# 07_-MCU.net
KiCad netlist of a schematic drawn in Altium Designer
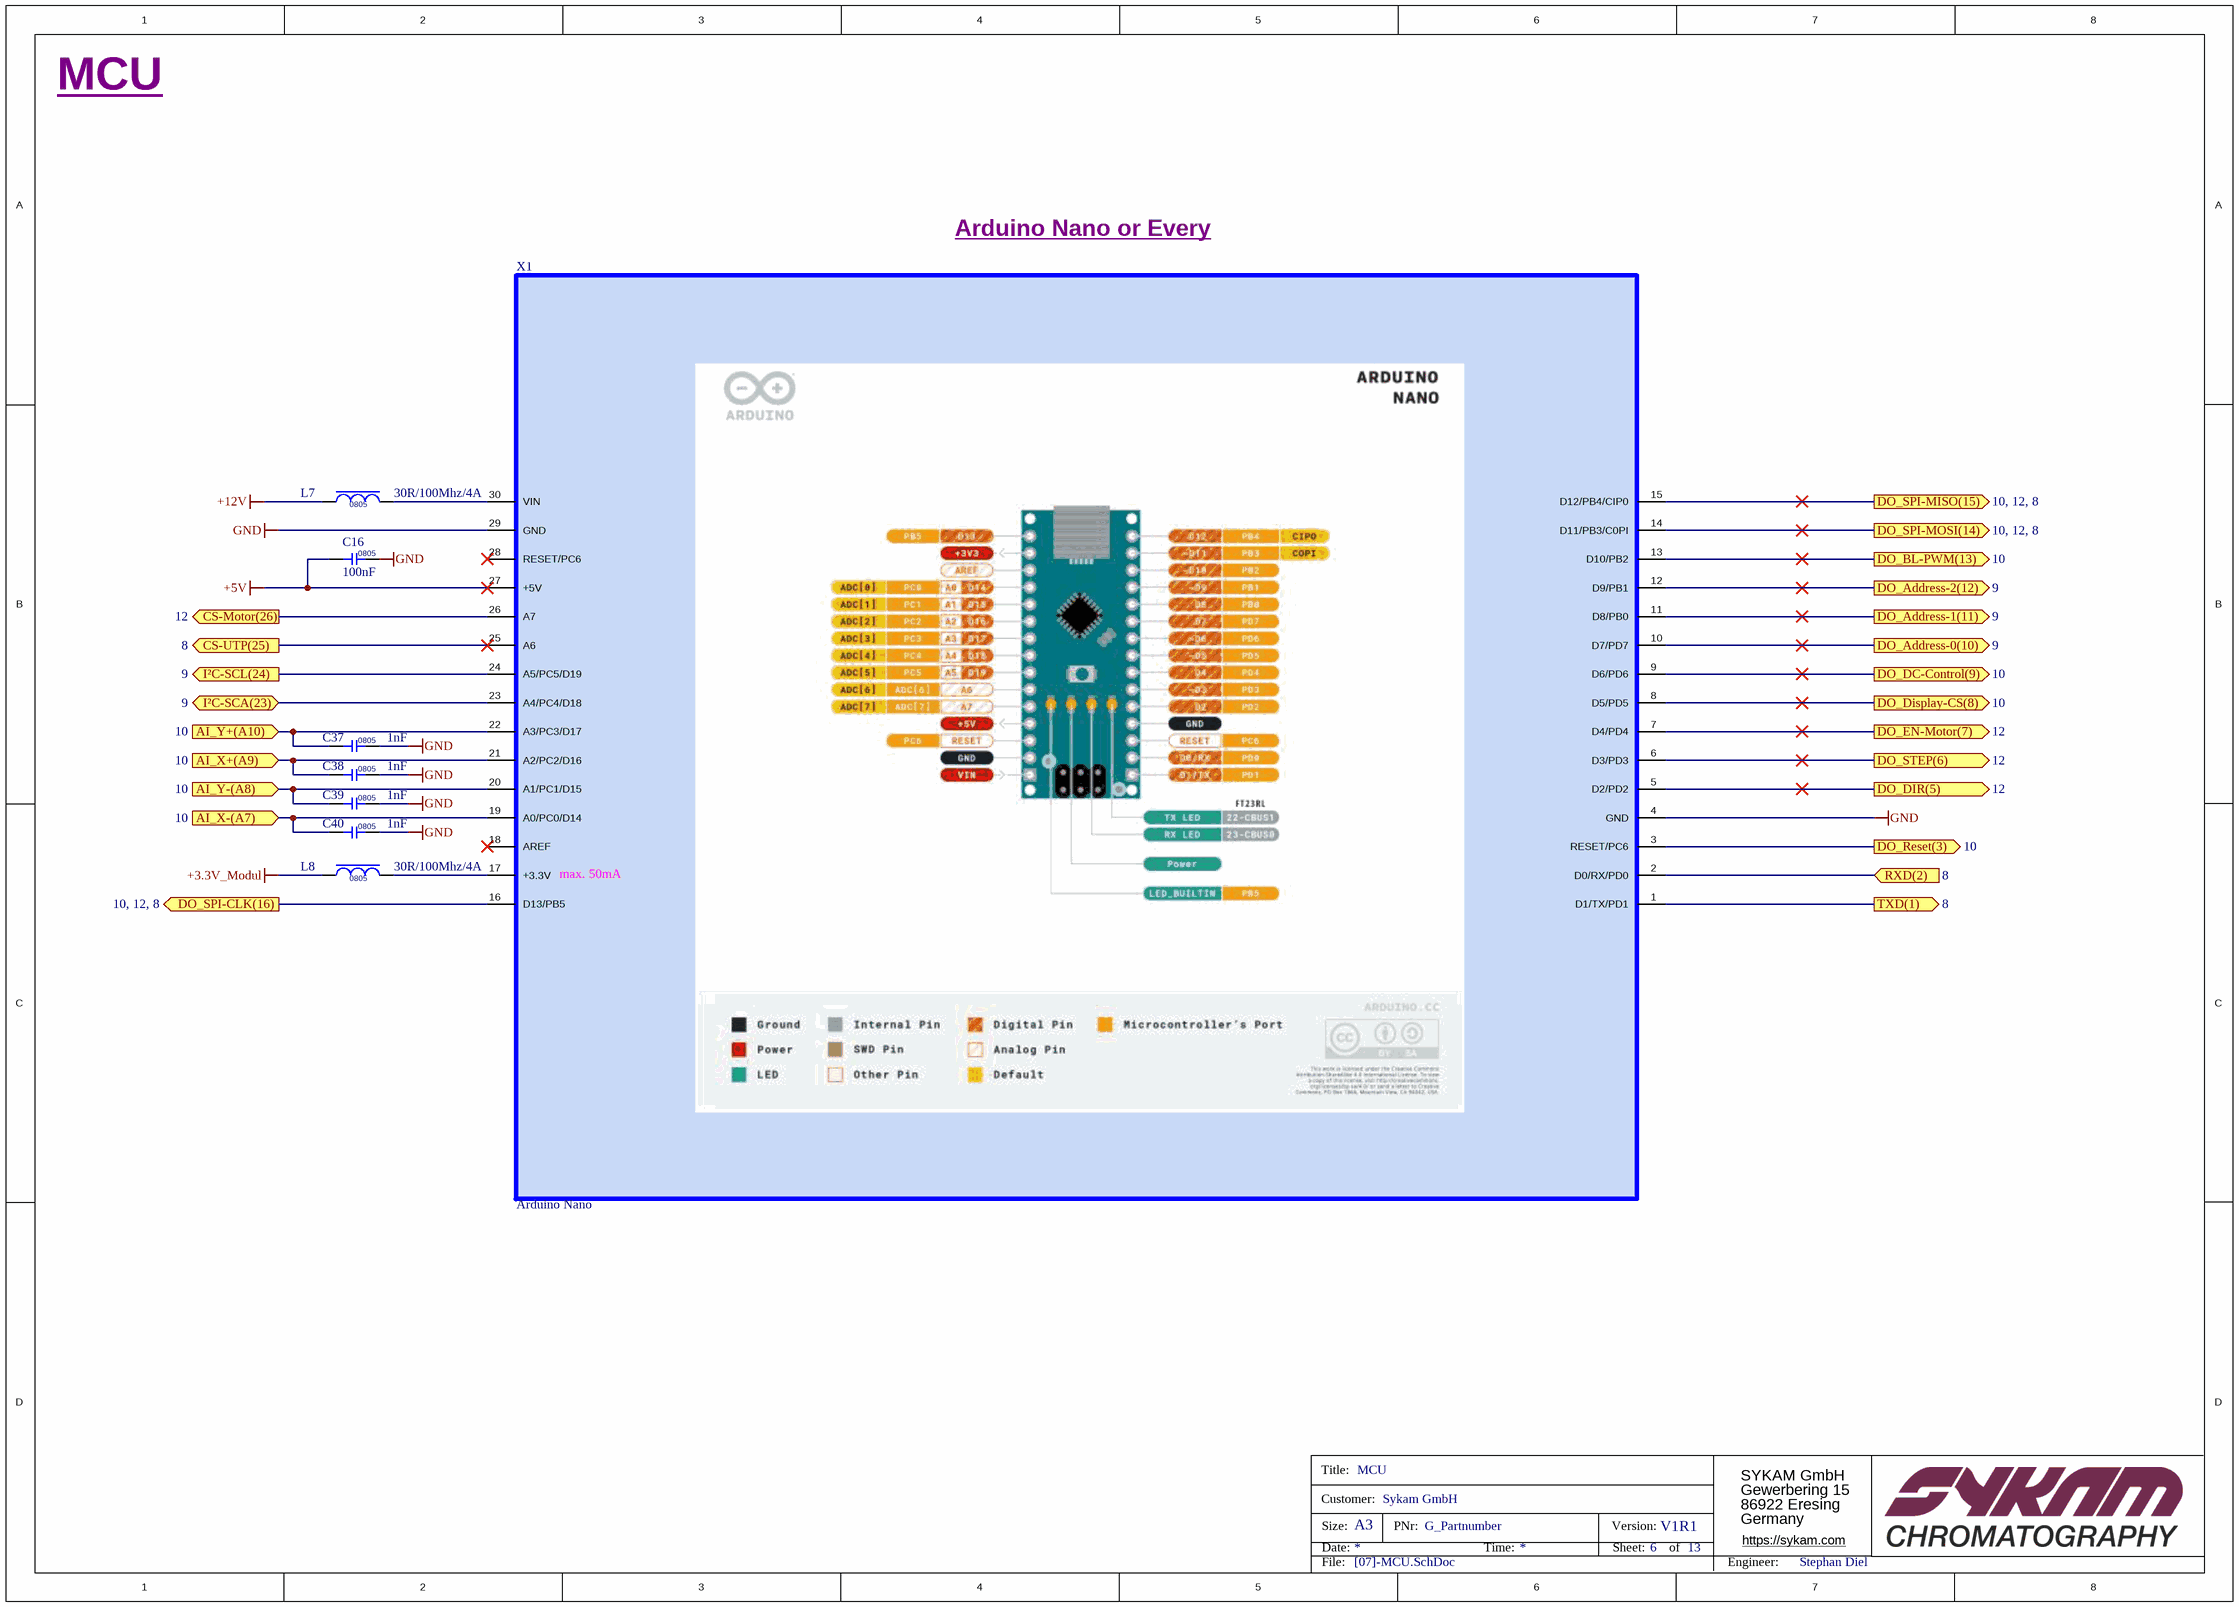
[diagram p0: [07]-MCU.SchDoc]

(export (version "E")
  (design (tool "Eeschema 10.0.6"))
  (components
    (comp (ref "C16")
      (value "100nF")
      (footprint "C0805")
      (description "CAP CER 0.1UF 50V X7R 0805")
      (fields
        (field (name "MANUFACTURER PART NUMBER") "CC0805KRX7R9BB104")
        (field (name "TOLERANCE") "10%")
        (field (name "PCBCHECKED") "initials after Checked")
        (field (name "SCHCHECKED") "Initials after checked")
      )
      (libsource (lib "ToradexMainBoard-V0I1") (part "C_100nF_CC0805KRX7R9BB104"))
    )
    (comp (ref "C37")
      (value "1nF")
      (footprint "C0805")
      (description "Multilayer Ceramic Capacitors MLCC - SMD/SMT 50volts 1000pF X7R 10%")
      (fields
        (field (name "MANUFACTURER") "KEMET")
        (field (name "MANUFACTURER PART NUMBER") "C0805C102K5RAC7411")
      )
      (libsource (lib "ToradexMainBoard-V0I1") (part "C_1nF_C0805C102K5RAC7411"))
    )
    (comp (ref "C38")
      (value "1nF")
      (footprint "C0805")
      (description "Multilayer Ceramic Capacitors MLCC - SMD/SMT 50volts 1000pF X7R 10%")
      (fields
        (field (name "MANUFACTURER") "KEMET")
        (field (name "MANUFACTURER PART NUMBER") "C0805C102K5RAC7411")
      )
      (libsource (lib "ToradexMainBoard-V0I1") (part "C_1nF_C0805C102K5RAC7411"))
    )
    (comp (ref "C39")
      (value "1nF")
      (footprint "C0805")
      (description "Multilayer Ceramic Capacitors MLCC - SMD/SMT 50volts 1000pF X7R 10%")
      (fields
        (field (name "MANUFACTURER") "KEMET")
        (field (name "MANUFACTURER PART NUMBER") "C0805C102K5RAC7411")
      )
      (libsource (lib "ToradexMainBoard-V0I1") (part "C_1nF_C0805C102K5RAC7411"))
    )
    (comp (ref "C40")
      (value "1nF")
      (footprint "C0805")
      (description "Multilayer Ceramic Capacitors MLCC - SMD/SMT 50volts 1000pF X7R 10%")
      (fields
        (field (name "MANUFACTURER") "KEMET")
        (field (name "MANUFACTURER PART NUMBER") "C0805C102K5RAC7411")
      )
      (libsource (lib "ToradexMainBoard-V0I1") (part "C_1nF_C0805C102K5RAC7411"))
    )
    (comp (ref "L7")
      (value "30R/100Mhz/4A")
      (footprint "L0805")
      (description "Ferrite Beads Multi-Layer 30Ohm 100MHz 4A 14mOhm DCR 0805 T/R")
      (fields
        (field (name "MANUFACTURER PART NUMBER") "BLM21PG300SN1D")
        (field (name "TOLERANCE") "25%")
        (field (name "PCBCHECKED") "initials after Checked")
        (field (name "SCHCHECKED") "Initials after checked")
      )
      (libsource (lib "ToradexMainBoard-V0I1") (part "L_BLM21PG300SN1D"))
    )
    (comp (ref "L8")
      (value "30R/100Mhz/4A")
      (footprint "L0805")
      (description "Ferrite Beads Multi-Layer 30Ohm 100MHz 4A 14mOhm DCR 0805 T/R")
      (fields
        (field (name "MANUFACTURER PART NUMBER") "BLM21PG300SN1D")
        (field (name "TOLERANCE") "25%")
        (field (name "PCBCHECKED") "initials after Checked")
        (field (name "SCHCHECKED") "Initials after checked")
      )
      (libsource (lib "ToradexMainBoard-V0I1") (part "L_BLM21PG300SN1D"))
    )
    (comp (ref "X1")
      (value "Arduino Nano")
      (footprint "Arduino-Nano-Connectors")
      (description "ATmega328 Microcontroller Development Board 16MHz CPU 2KB RAM 1KB/32KB EEPROM/Flash")
      (fields (field (name "MANUFACTURER") "Arduino") (field (name "MANUFACTURER PART NUMBER") "A000005"))
      (libsource (lib "ToradexMainBoard-V0I1") (part "CON_Modul_ArduinoNano3"))
    )
  )
  (nets
    (net (code "1") (name "+3.3V_Modul") (class "Default")
      (node (ref "L8") (pin "1") (pinfunction "1_1") (pintype "passive"))
    )
    (net (code "2") (name "+5V") (class "Default")
      (node (ref "C16") (pin "1") (pinfunction "1_1") (pintype "passive"))
      (node (ref "X1") (pin "27") (pinfunction "+5V_27") (pintype "passive"))
    )
    (net (code "3") (name "+12V") (class "Default")
      (node (ref "L7") (pin "1") (pinfunction "1_1") (pintype "passive"))
    )
    (net (code "4") (name "/AI_X+(A9)") (class "Default")
      (node (ref "C38") (pin "1") (pinfunction "1_1") (pintype "passive"))
      (node (ref "X1") (pin "21") (pinfunction "A2/PC2/D16_21") (pintype "passive"))
    )
    (net (code "5") (name "/AI_X-(A7)") (class "Default")
      (node (ref "C40") (pin "1") (pinfunction "1_1") (pintype "passive"))
      (node (ref "X1") (pin "19") (pinfunction "A0/PC0/D14_19") (pintype "passive"))
    )
    (net (code "6") (name "/AI_Y+(A10)") (class "Default")
      (node (ref "C37") (pin "1") (pinfunction "1_1") (pintype "passive"))
      (node (ref "X1") (pin "22") (pinfunction "A3/PC3/D17_22") (pintype "passive"))
    )
    (net (code "7") (name "/AI_Y-(A8)") (class "Default")
      (node (ref "C39") (pin "1") (pinfunction "1_1") (pintype "passive"))
      (node (ref "X1") (pin "20") (pinfunction "A1/PC1/D15_20") (pintype "passive"))
    )
    (net (code "8") (name "/CS-Motor(26)") (class "Default")
      (node (ref "X1") (pin "26") (pinfunction "A7_26") (pintype "passive"))
    )
    (net (code "9") (name "/CS-UTP(25)") (class "Default")
      (node (ref "X1") (pin "25") (pinfunction "A6_25") (pintype "passive+no_connect"))
    )
    (net (code "10") (name "/DO_Address-0(10)") (class "Default")
      (node (ref "X1") (pin "10") (pinfunction "D7/PD7_10") (pintype "passive"))
    )
    (net (code "11") (name "/DO_Address-1(11)") (class "Default")
      (node (ref "X1") (pin "11") (pinfunction "D8/PB0_11") (pintype "passive"))
    )
    (net (code "12") (name "/DO_Address-2(12)") (class "Default")
      (node (ref "X1") (pin "12") (pinfunction "D9/PB1_12") (pintype "passive"))
    )
    (net (code "13") (name "/DO_BL-PWM(13)") (class "Default")
      (node (ref "X1") (pin "13") (pinfunction "D10/PB2_13") (pintype "passive"))
    )
    (net (code "14") (name "/DO_DC-Control(9)") (class "Default")
      (node (ref "X1") (pin "9") (pinfunction "D6/PD6_9") (pintype "passive"))
    )
    (net (code "15") (name "/DO_DIR(5)") (class "Default")
      (node (ref "X1") (pin "5") (pinfunction "D2/PD2_5") (pintype "passive"))
    )
    (net (code "16") (name "/DO_Display-CS(8)") (class "Default")
      (node (ref "X1") (pin "8") (pinfunction "D5/PD5_8") (pintype "passive"))
    )
    (net (code "17") (name "/DO_EN-Motor(7)") (class "Default")
      (node (ref "X1") (pin "7") (pinfunction "D4/PD4_7") (pintype "passive"))
    )
    (net (code "18") (name "/DO_Reset(3)") (class "Default")
      (node (ref "X1") (pin "3") (pinfunction "RESET/PC6_3") (pintype "passive"))
    )
    (net (code "19") (name "/DO_SPI-CLK(16)") (class "Default")
      (node (ref "X1") (pin "16") (pinfunction "D13/PB5_16") (pintype "passive"))
    )
    (net (code "20") (name "/DO_SPI-MISO(15)") (class "Default")
      (node (ref "X1") (pin "15") (pinfunction "D12/PB4/CIP0_15") (pintype "passive"))
    )
    (net (code "21") (name "/DO_SPI-MOSI(14)") (class "Default")
      (node (ref "X1") (pin "14") (pinfunction "D11/PB3/C0PI_14") (pintype "passive"))
    )
    (net (code "22") (name "/DO_STEP(6)") (class "Default")
      (node (ref "X1") (pin "6") (pinfunction "D3/PD3_6") (pintype "passive"))
    )
    (net (code "23") (name "/I²C-SCA(23)") (class "Default")
      (node (ref "X1") (pin "23") (pinfunction "A4/PC4/D18_23") (pintype "passive"))
    )
    (net (code "24") (name "/I²C-SCL(24)") (class "Default")
      (node (ref "X1") (pin "24") (pinfunction "A5/PC5/D19_24") (pintype "passive"))
    )
    (net (code "25") (name "/RXD(2)") (class "Default")
      (node (ref "X1") (pin "2") (pinfunction "D0/RX/PD0_2") (pintype "passive"))
    )
    (net (code "26") (name "/TXD(1)") (class "Default")
      (node (ref "X1") (pin "1") (pinfunction "D1/TX/PD1_1") (pintype "passive"))
    )
    (net (code "27") (name "GND") (class "Default")
      (node (ref "C16") (pin "2") (pinfunction "2_2") (pintype "passive"))
      (node (ref "C37") (pin "2") (pinfunction "2_2") (pintype "passive"))
      (node (ref "C38") (pin "2") (pinfunction "2_2") (pintype "passive"))
      (node (ref "C39") (pin "2") (pinfunction "2_2") (pintype "passive"))
      (node (ref "C40") (pin "2") (pinfunction "2_2") (pintype "passive"))
      (node (ref "X1") (pin "29") (pinfunction "GND_29") (pintype "passive"))
      (node (ref "X1") (pin "4") (pinfunction "GND_4") (pintype "passive"))
    )
    (net (code "28") (name "Net-(X1-+3.3V)") (class "Default")
      (node (ref "L8") (pin "2") (pinfunction "2_2") (pintype "passive"))
      (node (ref "X1") (pin "17") (pinfunction "+3.3V_17") (pintype "passive"))
    )
    (net (code "29") (name "Net-(X1-VIN)") (class "Default")
      (node (ref "L7") (pin "2") (pinfunction "2_2") (pintype "passive"))
      (node (ref "X1") (pin "30") (pinfunction "VIN_30") (pintype "passive"))
    )
    (net (code "30") (name "unconnected-(X1-AREF-Pad18)") (class "Default")
      (node (ref "X1") (pin "18") (pinfunction "AREF_18") (pintype "passive+no_connect"))
    )
    (net (code "31") (name "unconnected-(X1-RESET{slash}PC6-Pad28)") (class "Default")
      (node (ref "X1") (pin "28") (pinfunction "RESET/PC6_28") (pintype "passive+no_connect"))
    )
  )
)
